# BCR_TempSense.net
KiCad netlist of a schematic drawn in Altium Designer
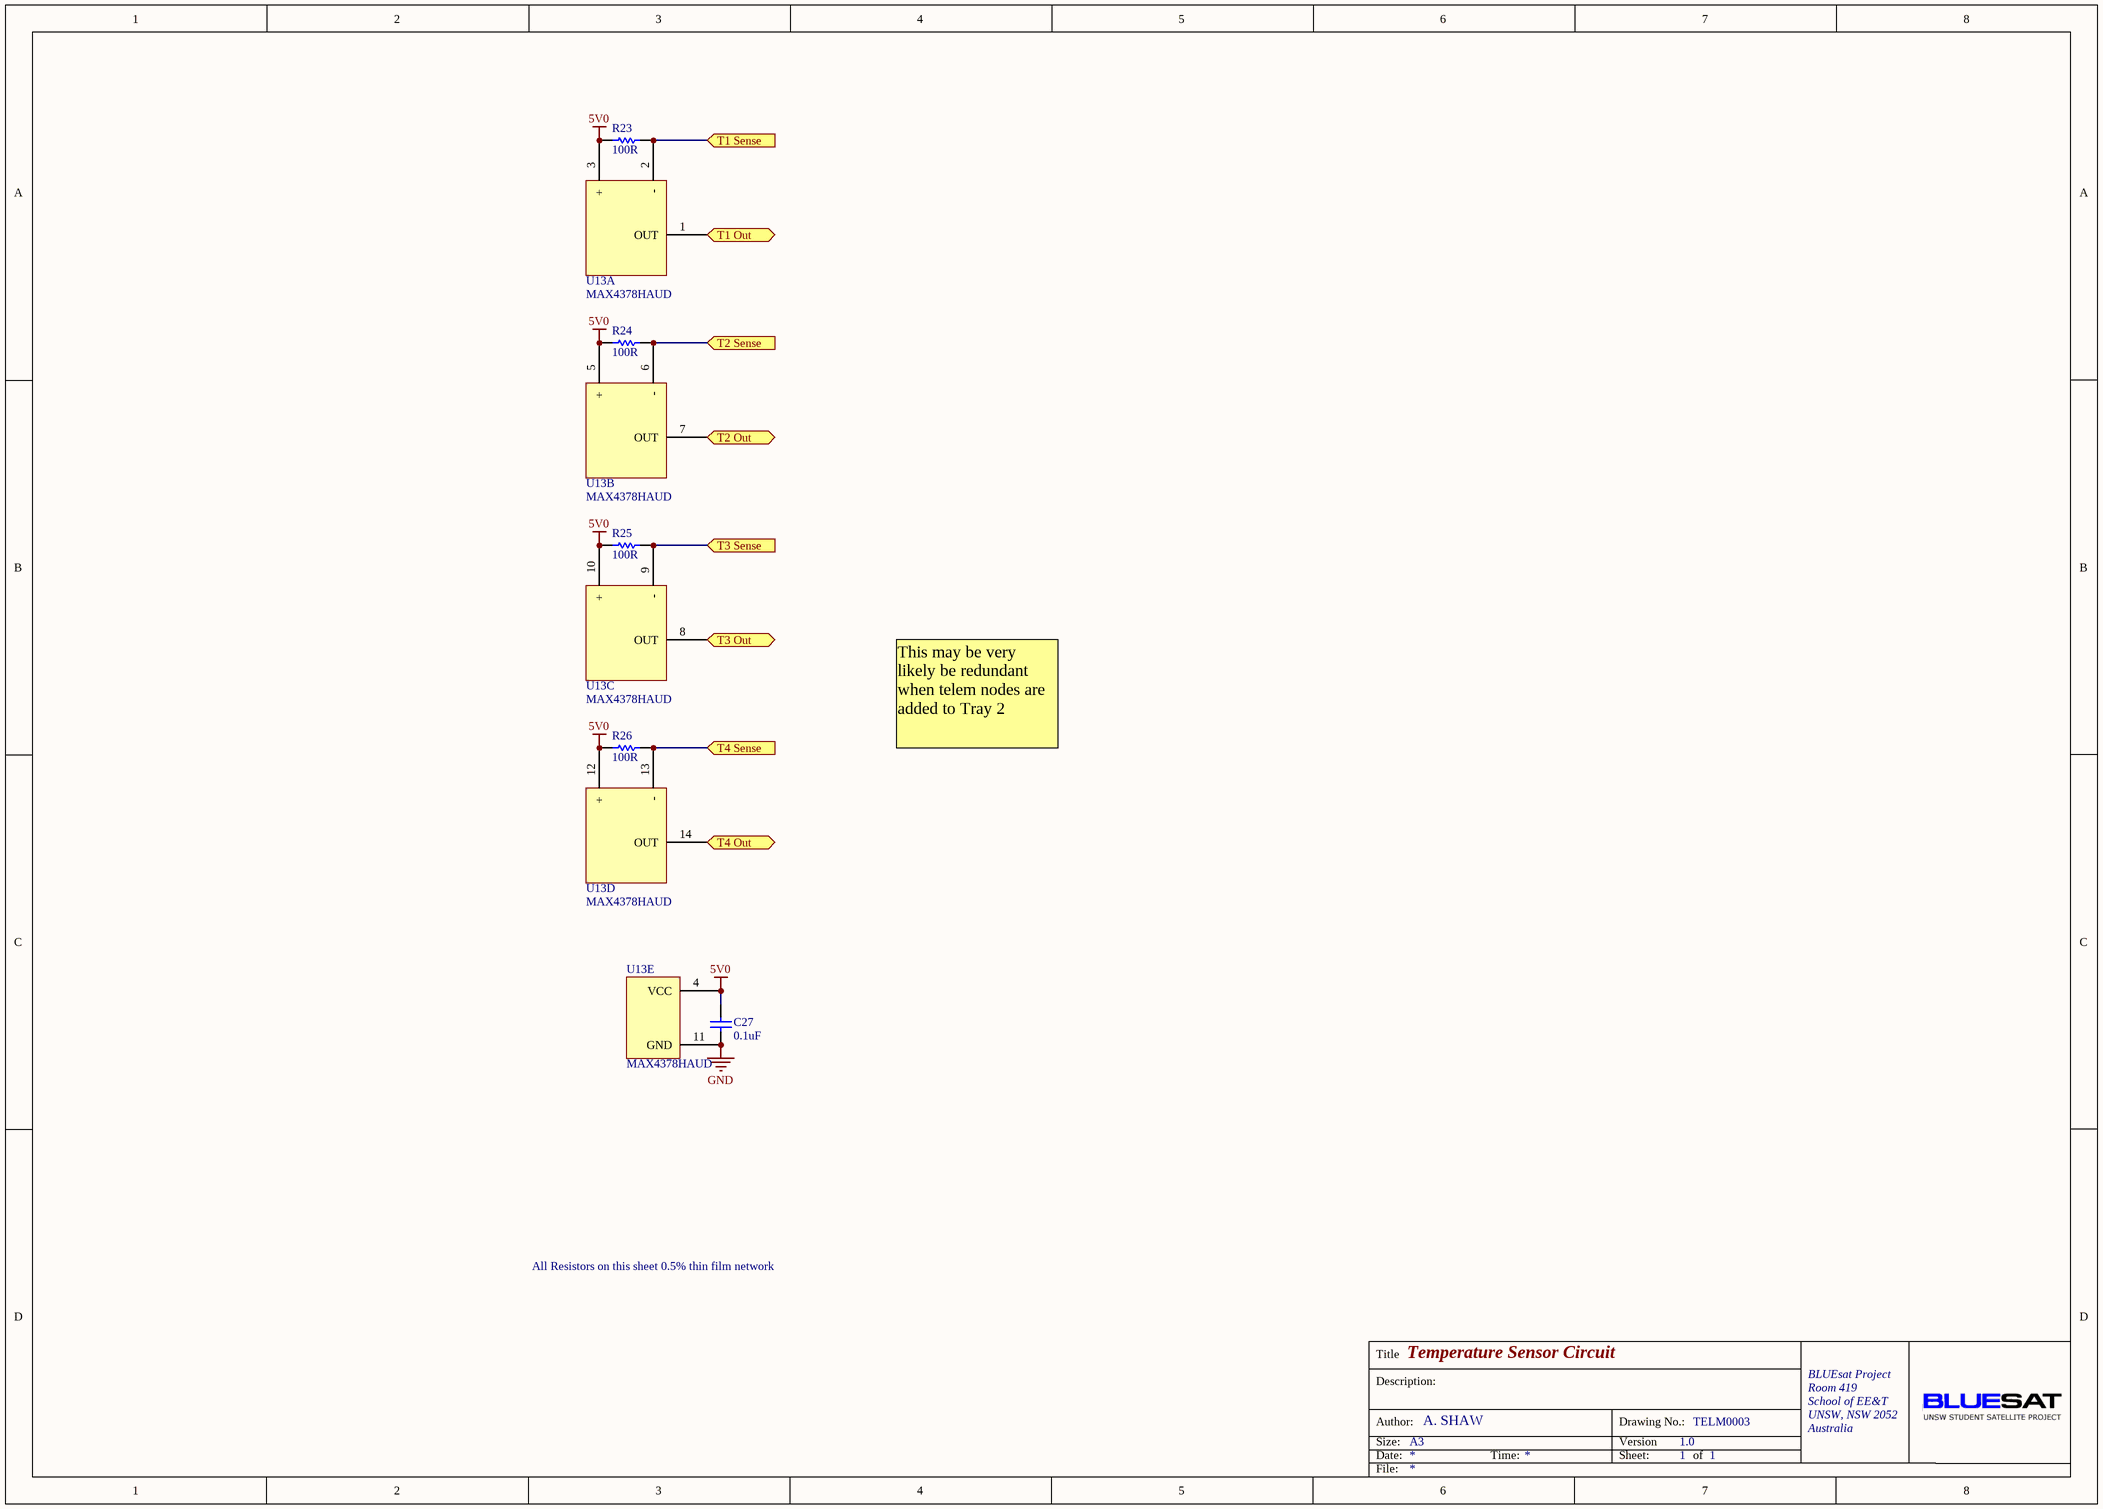
[diagram p0: BCR_TempSense.SchDoc]

(export (version "E")
  (design (tool "Eeschema 10.0.6"))
  (components
    (comp (ref "C27")
      (value "0.1uF")
      (footprint "CAPC2012M")
      (description "Capacitor")
      (fields (field (name "Comment") "Cap") (field (name "PUBLISHER") "Altium Limited"))
      (libsource (lib "Miscellaneous Devices") (part "Cap"))
    )
    (comp (ref "R23")
      (value "100R")
      (footprint "RESC2012M")
      (description "Resistor")
      (fields (field (name "Comment") "Res1") (field (name "PUBLISHER") "Altium Limited"))
      (libsource (lib "Miscellaneous Devices") (part "Res1"))
    )
    (comp (ref "R24")
      (value "100R")
      (footprint "RESC2012M")
      (description "Resistor")
      (fields (field (name "Comment") "Res1") (field (name "PUBLISHER") "Altium Limited"))
      (libsource (lib "Miscellaneous Devices") (part "Res1"))
    )
    (comp (ref "R25")
      (value "100R")
      (footprint "RESC2012M")
      (description "Resistor")
      (fields (field (name "Comment") "Res1") (field (name "PUBLISHER") "Altium Limited"))
      (libsource (lib "Miscellaneous Devices") (part "Res1"))
    )
    (comp (ref "R26")
      (value "100R")
      (footprint "RESC2012M")
      (description "Resistor")
      (fields (field (name "Comment") "Res1") (field (name "PUBLISHER") "Altium Limited"))
      (libsource (lib "Miscellaneous Devices") (part "Res1"))
    )
    (comp (ref "U13")
      (value "MAX4378HAUD")
      (footprint "TSOP65P640-14AN")
      (libsource (lib "Base") (part "MAX4378HAUD"))
    )
  )
  (nets
    (net (code "1") (name "/T1 Out") (class "Default")
      (node (ref "U13") (pin "1") (pinfunction "OUT_1") (pintype "passive"))
    )
    (net (code "2") (name "/T1 Sense") (class "Default")
      (node (ref "R23") (pin "2") (pinfunction "2_2") (pintype "passive"))
      (node (ref "U13") (pin "2") (pinfunction "-_2") (pintype "passive"))
    )
    (net (code "3") (name "/T2 Out") (class "Default")
      (node (ref "U13") (pin "7") (pinfunction "OUT_7") (pintype "passive"))
    )
    (net (code "4") (name "/T2 Sense") (class "Default")
      (node (ref "R24") (pin "2") (pinfunction "2_2") (pintype "passive"))
      (node (ref "U13") (pin "6") (pinfunction "-_6") (pintype "passive"))
    )
    (net (code "5") (name "/T3 Out") (class "Default")
      (node (ref "U13") (pin "8") (pinfunction "OUT_8") (pintype "passive"))
    )
    (net (code "6") (name "/T3 Sense") (class "Default")
      (node (ref "R25") (pin "2") (pinfunction "2_2") (pintype "passive"))
      (node (ref "U13") (pin "9") (pinfunction "-_9") (pintype "passive"))
    )
    (net (code "7") (name "/T4 Out") (class "Default")
      (node (ref "U13") (pin "14") (pinfunction "OUT_14") (pintype "passive"))
    )
    (net (code "8") (name "/T4 Sense") (class "Default")
      (node (ref "R26") (pin "2") (pinfunction "2_2") (pintype "passive"))
      (node (ref "U13") (pin "13") (pinfunction "-_13") (pintype "passive"))
    )
    (net (code "9") (name "5V0") (class "Default")
      (node (ref "C27") (pin "2") (pinfunction "2_2") (pintype "passive"))
      (node (ref "R23") (pin "1") (pinfunction "1_1") (pintype "passive"))
      (node (ref "R24") (pin "1") (pinfunction "1_1") (pintype "passive"))
      (node (ref "R25") (pin "1") (pinfunction "1_1") (pintype "passive"))
      (node (ref "R26") (pin "1") (pinfunction "1_1") (pintype "passive"))
      (node (ref "U13") (pin "10") (pinfunction "+_10") (pintype "passive"))
      (node (ref "U13") (pin "12") (pinfunction "+_12") (pintype "passive"))
      (node (ref "U13") (pin "3") (pinfunction "+_3") (pintype "passive"))
      (node (ref "U13") (pin "4") (pinfunction "VCC_4") (pintype "passive"))
      (node (ref "U13") (pin "5") (pinfunction "+_5") (pintype "passive"))
    )
    (net (code "10") (name "GND") (class "Default")
      (node (ref "C27") (pin "1") (pinfunction "1_1") (pintype "passive"))
      (node (ref "U13") (pin "11") (pinfunction "GND_11") (pintype "passive"))
    )
  )
)
